# HW2.net
KiCad netlist of a schematic drawn in EAGLE
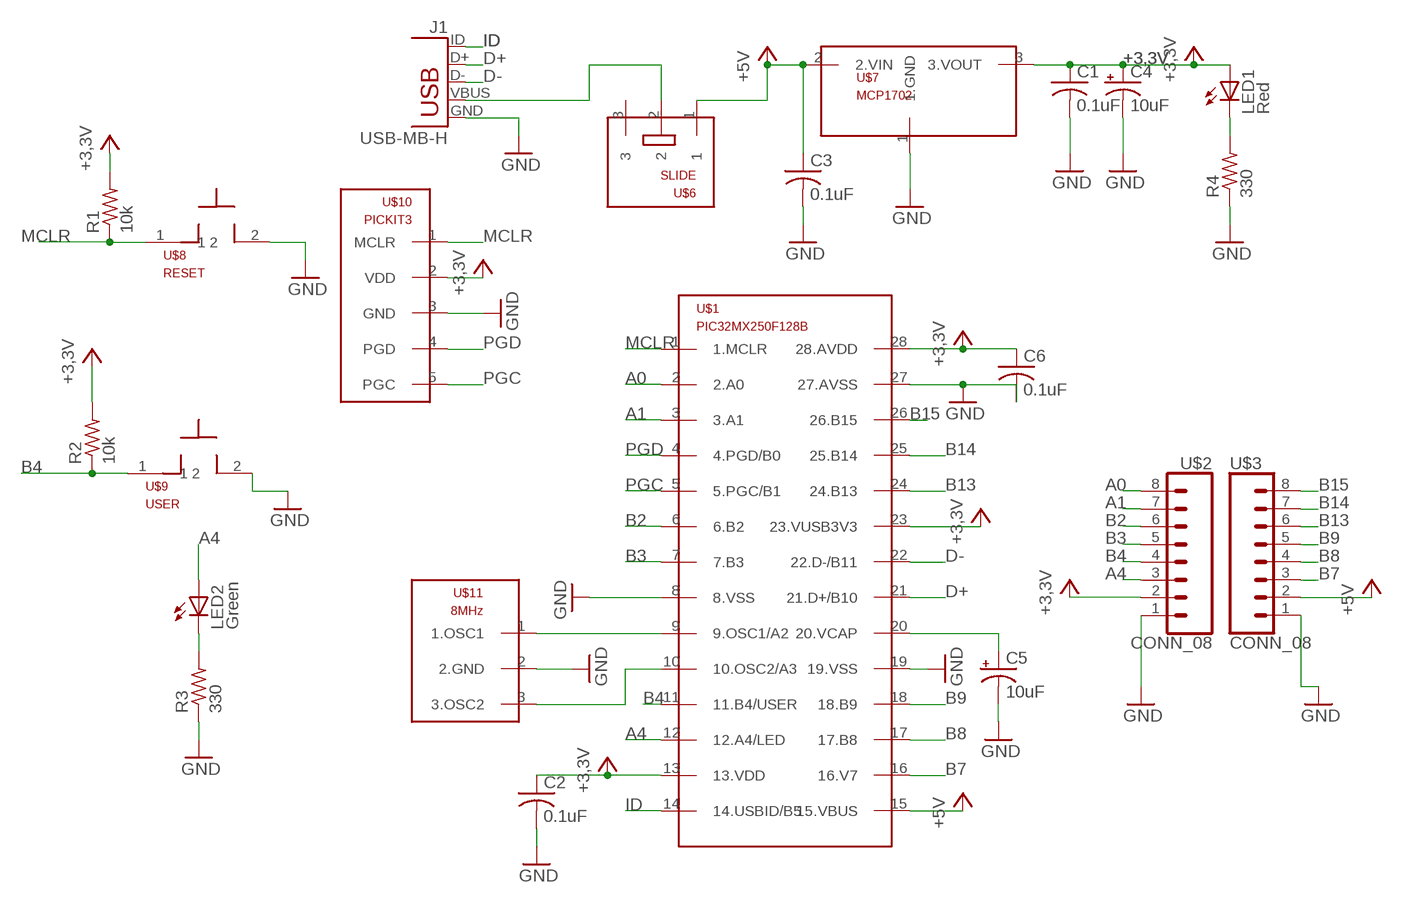
[diagram p0: schematic, sheet 1]

(export (version "E")
  (design (tool "Eeschema 10.0.6"))
  (components
    (comp (ref "C1")
      (value "0.1uF")
      (footprint "eagle-import:C025-025X050")
      (libsource (lib "eagle-import") (part "C-US025-025X050"))
    )
    (comp (ref "C2")
      (value "0.1uF")
      (footprint "eagle-import:C025-025X050")
      (libsource (lib "eagle-import") (part "C-US025-025X050"))
    )
    (comp (ref "C3")
      (value "0.1uF")
      (footprint "eagle-import:C025-025X050")
      (libsource (lib "eagle-import") (part "C-US025-025X050"))
    )
    (comp (ref "C4")
      (value "10uF")
      (footprint "eagle-import:B45181B")
      (libsource (lib "eagle-import") (part "CPOL-USB45181B"))
    )
    (comp (ref "C5")
      (value "10uF")
      (footprint "eagle-import:B45181B")
      (libsource (lib "eagle-import") (part "CPOL-USB45181B"))
    )
    (comp (ref "C6")
      (value "0.1uF")
      (footprint "eagle-import:C025-025X050")
      (libsource (lib "eagle-import") (part "C-US025-025X050"))
    )
    (comp (ref "J1")
      (value "USB-MB-H")
      (footprint "eagle-import:USB-MB-H")
      (libsource (lib "eagle-import") (part "USB-MB-H"))
    )
    (comp (ref "LED1")
      (value "Red")
      (footprint "eagle-import:LED3MM")
      (libsource (lib "eagle-import") (part "LED3MM"))
    )
    (comp (ref "LED2")
      (value "Green")
      (footprint "eagle-import:LED3MM")
      (libsource (lib "eagle-import") (part "LED3MM"))
    )
    (comp (ref "R1")
      (value "10k")
      (footprint "eagle-import:0207_10")
      (libsource (lib "eagle-import") (part "R-US_0207/10"))
    )
    (comp (ref "R2")
      (value "10k")
      (footprint "eagle-import:0207_10")
      (libsource (lib "eagle-import") (part "R-US_0207/10"))
    )
    (comp (ref "R3")
      (value "330")
      (footprint "eagle-import:0207_10")
      (libsource (lib "eagle-import") (part "R-US_0207/10"))
    )
    (comp (ref "R4")
      (value "330")
      (footprint "eagle-import:0207_10")
      (libsource (lib "eagle-import") (part "R-US_0207/10"))
    )
    (comp (ref "U$1")
      (value "PIC32MX250F128B")
      (footprint "eagle-import:DIL28-3")
      (libsource (lib "eagle-import") (part "PIC32MX250F128B"))
    )
    (comp (ref "U$2")
      (value "CONN_08")
      (footprint "eagle-import:1X08")
      (libsource (lib "eagle-import") (part "CONN_08"))
    )
    (comp (ref "U$3")
      (value "CONN_08")
      (footprint "eagle-import:1X08")
      (libsource (lib "eagle-import") (part "CONN_08"))
    )
    (comp (ref "U$6")
      (value "SLIDE")
      (footprint "eagle-import:SLIDE")
      (libsource (lib "eagle-import") (part "SLIDE"))
    )
    (comp (ref "U$7")
      (value "MCP1702")
      (footprint "eagle-import:TO92")
      (libsource (lib "eagle-import") (part "MCP1702"))
    )
    (comp (ref "U$8")
      (value "RESET")
      (footprint "eagle-import:PB")
      (libsource (lib "eagle-import") (part "PB"))
    )
    (comp (ref "U$9")
      (value "USER")
      (footprint "eagle-import:PB")
      (libsource (lib "eagle-import") (part "PB"))
    )
    (comp (ref "U$10")
      (value "PICKIT3")
      (footprint "eagle-import:1X05")
      (libsource (lib "eagle-import") (part "PICKIT3"))
    )
    (comp (ref "U$11")
      (value "8MHz")
      (footprint "eagle-import:OSC")
      (libsource (lib "eagle-import") (part "OSC"))
    )
  )
  (nets
    (net (code "1") (name "+3,3V") (class "Default")
      (node (ref "C1") (pin "1") (pinfunction "1_1") (pintype "passive"))
      (node (ref "C2") (pin "1") (pinfunction "1_1") (pintype "passive"))
      (node (ref "C4") (pin "+") (pinfunction "+_+") (pintype "passive"))
      (node (ref "C6") (pin "1") (pinfunction "1_1") (pintype "passive"))
      (node (ref "LED1") (pin "A") (pinfunction "A_A") (pintype "passive"))
      (node (ref "R1") (pin "2") (pinfunction "2_2") (pintype "passive"))
      (node (ref "R2") (pin "2") (pinfunction "2_2") (pintype "passive"))
      (node (ref "U$1") (pin "13") (pinfunction "13.VDD_13") (pintype "bidirectional"))
      (node (ref "U$1") (pin "23") (pinfunction "23.VUSB3V3_23") (pintype "bidirectional"))
      (node (ref "U$1") (pin "28") (pinfunction "28.AVDD_28") (pintype "bidirectional"))
      (node (ref "U$10") (pin "2") (pinfunction "VDD_2") (pintype "bidirectional"))
      (node (ref "U$2") (pin "2") (pinfunction "2_2") (pintype "passive"))
      (node (ref "U$7") (pin "3") (pinfunction "3.VOUT_3") (pintype "bidirectional"))
    )
    (net (code "2") (name "+5V") (class "Default")
      (node (ref "C3") (pin "1") (pinfunction "1_1") (pintype "passive"))
      (node (ref "U$1") (pin "15") (pinfunction "15.VBUS_15") (pintype "bidirectional"))
      (node (ref "U$3") (pin "2") (pinfunction "2_2") (pintype "passive"))
      (node (ref "U$6") (pin "1") (pinfunction "1_1") (pintype "bidirectional"))
      (node (ref "U$7") (pin "2") (pinfunction "2.VIN_2") (pintype "bidirectional"))
    )
    (net (code "3") (name "/A0") (class "Default")
      (node (ref "U$1") (pin "2") (pinfunction "2.A0_2") (pintype "bidirectional"))
      (node (ref "U$2") (pin "8") (pinfunction "8_8") (pintype "passive"))
    )
    (net (code "4") (name "/A1") (class "Default")
      (node (ref "U$1") (pin "3") (pinfunction "3.A1_3") (pintype "bidirectional"))
      (node (ref "U$2") (pin "7") (pinfunction "7_7") (pintype "passive"))
    )
    (net (code "5") (name "/A4") (class "Default")
      (node (ref "LED2") (pin "A") (pinfunction "A_A") (pintype "passive"))
      (node (ref "U$1") (pin "12") (pinfunction "12.A4/LED_12") (pintype "bidirectional"))
      (node (ref "U$2") (pin "3") (pinfunction "3_3") (pintype "passive"))
    )
    (net (code "6") (name "/B2") (class "Default")
      (node (ref "U$1") (pin "6") (pinfunction "6.B2_6") (pintype "bidirectional"))
      (node (ref "U$2") (pin "6") (pinfunction "6_6") (pintype "passive"))
    )
    (net (code "7") (name "/B3") (class "Default")
      (node (ref "U$1") (pin "7") (pinfunction "7.B3_7") (pintype "bidirectional"))
      (node (ref "U$2") (pin "5") (pinfunction "5_5") (pintype "passive"))
    )
    (net (code "8") (name "/B4") (class "Default")
      (node (ref "R2") (pin "1") (pinfunction "1_1") (pintype "passive"))
      (node (ref "U$1") (pin "11") (pinfunction "11.B4/USER_11") (pintype "bidirectional"))
      (node (ref "U$2") (pin "4") (pinfunction "4_4") (pintype "passive"))
      (node (ref "U$9") (pin "1") (pinfunction "1_1") (pintype "bidirectional"))
    )
    (net (code "9") (name "/B7") (class "Default")
      (node (ref "U$1") (pin "16") (pinfunction "16.V7_16") (pintype "bidirectional"))
      (node (ref "U$3") (pin "3") (pinfunction "3_3") (pintype "passive"))
    )
    (net (code "10") (name "/B8") (class "Default")
      (node (ref "U$1") (pin "17") (pinfunction "17.B8_17") (pintype "bidirectional"))
      (node (ref "U$3") (pin "4") (pinfunction "4_4") (pintype "passive"))
    )
    (net (code "11") (name "/B9") (class "Default")
      (node (ref "U$1") (pin "18") (pinfunction "18.B9_18") (pintype "bidirectional"))
      (node (ref "U$3") (pin "5") (pinfunction "5_5") (pintype "passive"))
    )
    (net (code "12") (name "/B13") (class "Default")
      (node (ref "U$1") (pin "24") (pinfunction "24.B13_24") (pintype "bidirectional"))
      (node (ref "U$3") (pin "6") (pinfunction "6_6") (pintype "passive"))
    )
    (net (code "13") (name "/B14") (class "Default")
      (node (ref "U$1") (pin "25") (pinfunction "25.B14_25") (pintype "bidirectional"))
      (node (ref "U$3") (pin "7") (pinfunction "7_7") (pintype "passive"))
    )
    (net (code "14") (name "/B15") (class "Default")
      (node (ref "U$1") (pin "26") (pinfunction "26.B15_26") (pintype "bidirectional"))
      (node (ref "U$3") (pin "8") (pinfunction "8_8") (pintype "passive"))
    )
    (net (code "15") (name "/D+") (class "Default")
      (node (ref "J1") (pin "D+") (pinfunction "D+_D+") (pintype "bidirectional"))
      (node (ref "U$1") (pin "21") (pinfunction "21.D+/B10_21") (pintype "bidirectional"))
    )
    (net (code "16") (name "/D-") (class "Default")
      (node (ref "J1") (pin "D-") (pinfunction "D-_D-") (pintype "bidirectional"))
      (node (ref "U$1") (pin "22") (pinfunction "22.D-/B11_22") (pintype "bidirectional"))
    )
    (net (code "17") (name "/ID") (class "Default")
      (node (ref "J1") (pin "ID") (pinfunction "ID_ID") (pintype "bidirectional"))
      (node (ref "U$1") (pin "14") (pinfunction "14.USBID/B5_14") (pintype "bidirectional"))
    )
    (net (code "18") (name "/MCLR") (class "Default")
      (node (ref "R1") (pin "1") (pinfunction "1_1") (pintype "passive"))
      (node (ref "U$1") (pin "1") (pinfunction "1.MCLR_1") (pintype "bidirectional"))
      (node (ref "U$10") (pin "1") (pinfunction "MCLR_1") (pintype "bidirectional"))
      (node (ref "U$8") (pin "1") (pinfunction "1_1") (pintype "bidirectional"))
    )
    (net (code "19") (name "/PGC") (class "Default")
      (node (ref "U$1") (pin "5") (pinfunction "5.PGC/B1_5") (pintype "bidirectional"))
      (node (ref "U$10") (pin "5") (pinfunction "PGC_5") (pintype "bidirectional"))
    )
    (net (code "20") (name "/PGD") (class "Default")
      (node (ref "U$1") (pin "4") (pinfunction "4.PGD/B0_4") (pintype "bidirectional"))
      (node (ref "U$10") (pin "4") (pinfunction "PGD_4") (pintype "bidirectional"))
    )
    (net (code "21") (name "GND") (class "Default")
      (node (ref "C1") (pin "2") (pinfunction "2_2") (pintype "passive"))
      (node (ref "C2") (pin "2") (pinfunction "2_2") (pintype "passive"))
      (node (ref "C3") (pin "2") (pinfunction "2_2") (pintype "passive"))
      (node (ref "C4") (pin "-") (pinfunction "-_-") (pintype "passive"))
      (node (ref "C5") (pin "-") (pinfunction "-_-") (pintype "passive"))
      (node (ref "C6") (pin "2") (pinfunction "2_2") (pintype "passive"))
      (node (ref "J1") (pin "GND") (pinfunction "GND_GND") (pintype "bidirectional"))
      (node (ref "R3") (pin "1") (pinfunction "1_1") (pintype "passive"))
      (node (ref "R4") (pin "1") (pinfunction "1_1") (pintype "passive"))
      (node (ref "U$1") (pin "19") (pinfunction "19.VSS_19") (pintype "bidirectional"))
      (node (ref "U$1") (pin "27") (pinfunction "27.AVSS_27") (pintype "bidirectional"))
      (node (ref "U$1") (pin "8") (pinfunction "8.VSS_8") (pintype "bidirectional"))
      (node (ref "U$10") (pin "3") (pinfunction "GND_3") (pintype "bidirectional"))
      (node (ref "U$11") (pin "2") (pinfunction "2.GND_2") (pintype "bidirectional"))
      (node (ref "U$2") (pin "1") (pinfunction "1_1") (pintype "passive"))
      (node (ref "U$3") (pin "1") (pinfunction "1_1") (pintype "passive"))
      (node (ref "U$7") (pin "1") (pinfunction "1.GND_1") (pintype "bidirectional"))
      (node (ref "U$8") (pin "2") (pinfunction "2_2") (pintype "bidirectional"))
      (node (ref "U$9") (pin "2") (pinfunction "2_2") (pintype "bidirectional"))
    )
    (net (code "22") (name "Net-(J1-PadVBUS)") (class "Default")
      (node (ref "J1") (pin "VBUS") (pinfunction "VBUS_VBUS") (pintype "bidirectional"))
      (node (ref "U$6") (pin "2") (pinfunction "2_2") (pintype "bidirectional"))
    )
    (net (code "23") (name "Net-(LED1-C)") (class "Default")
      (node (ref "LED1") (pin "K") (pinfunction "C_K") (pintype "passive"))
      (node (ref "R4") (pin "2") (pinfunction "2_2") (pintype "passive"))
    )
    (net (code "24") (name "Net-(LED2-C)") (class "Default")
      (node (ref "LED2") (pin "K") (pinfunction "C_K") (pintype "passive"))
      (node (ref "R3") (pin "2") (pinfunction "2_2") (pintype "passive"))
    )
    (net (code "25") (name "Net-(U$1-9.OSC1{slash}A2)") (class "Default")
      (node (ref "U$1") (pin "9") (pinfunction "9.OSC1/A2_9") (pintype "bidirectional"))
      (node (ref "U$11") (pin "1") (pinfunction "1.OSC1_1") (pintype "bidirectional"))
    )
    (net (code "26") (name "Net-(U$1-10.OSC2{slash}A3)") (class "Default")
      (node (ref "U$1") (pin "10") (pinfunction "10.OSC2/A3_10") (pintype "bidirectional"))
      (node (ref "U$11") (pin "3") (pinfunction "3.OSC2_3") (pintype "bidirectional"))
    )
    (net (code "27") (name "Net-(U$1-20.VCAP)") (class "Default")
      (node (ref "C5") (pin "+") (pinfunction "+_+") (pintype "passive"))
      (node (ref "U$1") (pin "20") (pinfunction "20.VCAP_20") (pintype "bidirectional"))
    )
    (net (code "28") (name "unconnected-(U$6-Pad3)") (class "Default")
      (node (ref "U$6") (pin "3") (pinfunction "3_3") (pintype "bidirectional"))
    )
  )
)
